# ac-to-dc.net
KiCad netlist of a schematic drawn in EAGLE
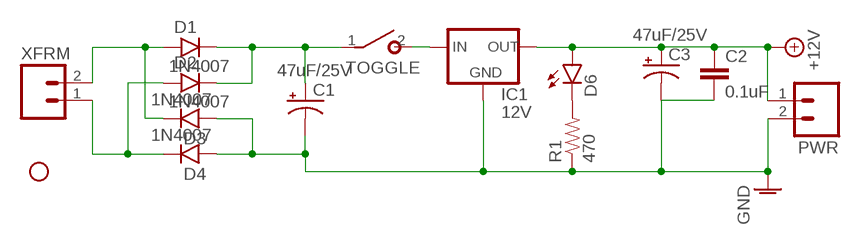
[diagram p0: schematic, sheet 1]

(export (version "E")
  (design (tool "Eeschema 10.0.6"))
  (components
    (comp (ref "C1")
      (value "47uF/25V")
      (footprint "eagle-import:E2,5-6")
      (libsource (lib "eagle-import") (part "CPOL-USE2.5-6"))
    )
    (comp (ref "C2")
      (value "0.1uF")
      (footprint "eagle-import:CAP-PTH-SMALL")
      (libsource (lib "eagle-import") (part "CAPPTH"))
    )
    (comp (ref "C3")
      (value "47uF/25V")
      (footprint "eagle-import:E2,5-6")
      (libsource (lib "eagle-import") (part "CPOL-USE2.5-6"))
    )
    (comp (ref "D1")
      (value "1N4007")
      (footprint "eagle-import:DO41-3")
      (libsource (lib "eagle-import") (part "1N400X.3"))
    )
    (comp (ref "D2")
      (value "1N4007")
      (footprint "eagle-import:DO41-3")
      (libsource (lib "eagle-import") (part "1N400X.3"))
    )
    (comp (ref "D3")
      (value "1N4007")
      (footprint "eagle-import:DO41-3")
      (libsource (lib "eagle-import") (part "1N400X.3"))
    )
    (comp (ref "D4")
      (value "1N4007")
      (footprint "eagle-import:DO41-3")
      (libsource (lib "eagle-import") (part "1N400X.3"))
    )
    (comp (ref "D6")
      (value "LED-3MM-NO_SILK")
      (footprint "eagle-import:LED3MM-NS")
      (libsource (lib "eagle-import") (part "LED-3MM-NO_SILK"))
    )
    (comp (ref "IC1")
      (value "12V")
      (footprint "eagle-import:78XXS")
      (libsource (lib "eagle-import") (part "78XXS"))
    )
    (comp (ref "JP1")
      (value "STAND-OFF")
      (footprint "eagle-import:STAND-OFF")
      (libsource (lib "eagle-import") (part "STAND-OFF"))
    )
    (comp (ref "PWR")
      (value "M02PTH")
      (footprint "eagle-import:1X02")
      (libsource (lib "eagle-import") (part "M02PTH"))
    )
    (comp (ref "R1")
      (value "470")
      (footprint "eagle-import:AXIAL-0.4")
      (libsource (lib "eagle-import") (part "RESISTORPTH-1/4W"))
    )
    (comp (ref "TOGGLE")
      (value "SPST")
      (footprint "eagle-import:SPST")
      (libsource (lib "eagle-import") (part "SPST"))
    )
    (comp (ref "XFRM")
      (value "M02PTH")
      (footprint "eagle-import:1X02")
      (libsource (lib "eagle-import") (part "M02PTH"))
    )
  )
  (nets
    (net (code "1") (name "+12V") (class "Default")
      (node (ref "C2") (pin "1") (pinfunction "1_1") (pintype "passive"))
      (node (ref "C3") (pin "+") (pinfunction "+_+") (pintype "passive"))
      (node (ref "D6") (pin "A") (pinfunction "A_A") (pintype "passive"))
      (node (ref "IC1") (pin "OUT") (pinfunction "OUT_OUT") (pintype "passive"))
      (node (ref "PWR") (pin "1") (pinfunction "1_1") (pintype "passive"))
    )
    (net (code "2") (name "GND") (class "Default")
      (node (ref "C1") (pin "-") (pinfunction "-_-") (pintype "passive"))
      (node (ref "C2") (pin "2") (pinfunction "2_2") (pintype "passive"))
      (node (ref "C3") (pin "-") (pinfunction "-_-") (pintype "passive"))
      (node (ref "D3") (pin "A") (pinfunction "A_A") (pintype "passive"))
      (node (ref "D4") (pin "A") (pinfunction "A_A") (pintype "passive"))
      (node (ref "IC1") (pin "GND") (pinfunction "GND_GND") (pintype "input"))
      (node (ref "PWR") (pin "2") (pinfunction "2_2") (pintype "passive"))
      (node (ref "R1") (pin "P$1") (pinfunction "1_P$1") (pintype "passive"))
    )
    (net (code "3") (name "Net-(D1-PadA)") (class "Default")
      (node (ref "D1") (pin "A") (pinfunction "A_A") (pintype "passive"))
      (node (ref "D3") (pin "C") (pinfunction "C_C") (pintype "passive"))
      (node (ref "XFRM") (pin "2") (pinfunction "2_2") (pintype "passive"))
    )
    (net (code "4") (name "Net-(D2-PadA)") (class "Default")
      (node (ref "D2") (pin "A") (pinfunction "A_A") (pintype "passive"))
      (node (ref "D4") (pin "C") (pinfunction "C_C") (pintype "passive"))
      (node (ref "XFRM") (pin "1") (pinfunction "1_1") (pintype "passive"))
    )
    (net (code "5") (name "Net-(D6-C)") (class "Default")
      (node (ref "D6") (pin "K") (pinfunction "C_K") (pintype "passive"))
      (node (ref "R1") (pin "P$2") (pinfunction "2_P$2") (pintype "passive"))
    )
    (net (code "6") (name "Net-(TOGGLE-P)") (class "Default")
      (node (ref "C1") (pin "+") (pinfunction "+_+") (pintype "passive"))
      (node (ref "D1") (pin "C") (pinfunction "C_C") (pintype "passive"))
      (node (ref "D2") (pin "C") (pinfunction "C_C") (pintype "passive"))
      (node (ref "TOGGLE") (pin "1") (pinfunction "P_1") (pintype "passive"))
    )
    (net (code "7") (name "Net-(TOGGLE-S)") (class "Default")
      (node (ref "IC1") (pin "IN") (pinfunction "IN_IN") (pintype "input"))
      (node (ref "TOGGLE") (pin "2") (pinfunction "S_2") (pintype "passive"))
    )
  )
)
